# 2022_AESK_UAV_Sensors.net
KiCad netlist of a schematic drawn in Altium Designer
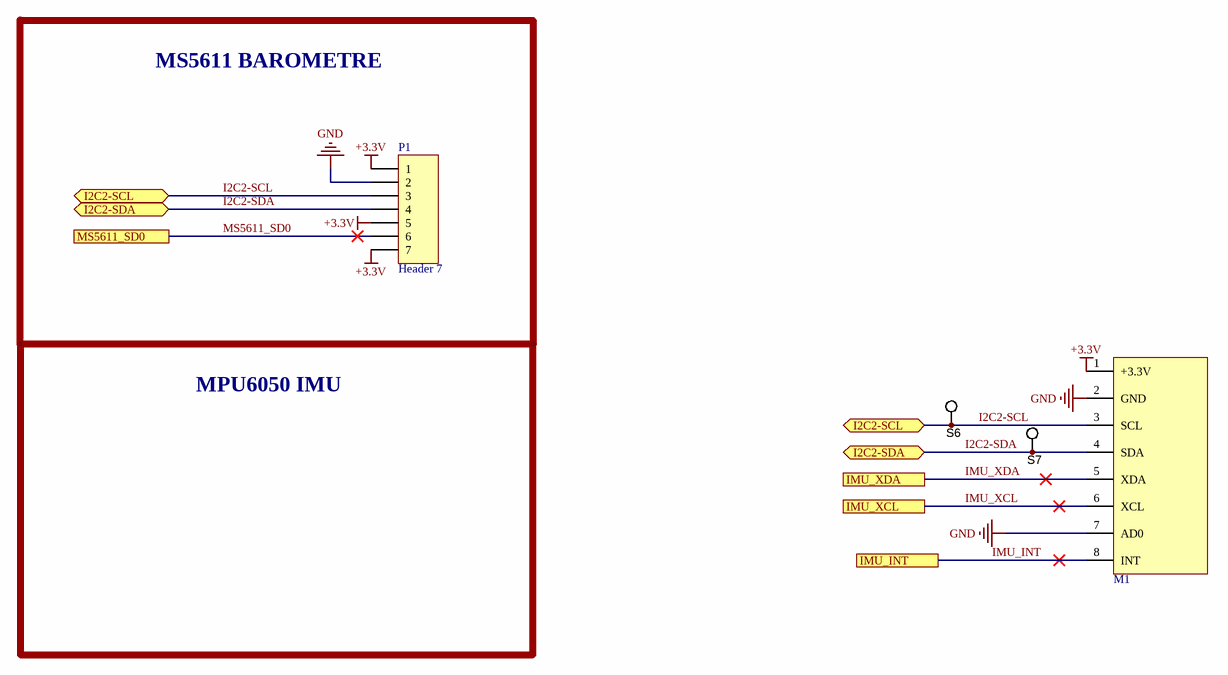
[diagram p0: 2022_AESK_UAV_Sensors.SchDoc]

(export (version "E")
  (design (tool "Eeschema 10.0.6"))
  (components
    (comp (ref "M1")
      (value "MPU-9255(resim ve supplier bilgileri mpu6050dir)")
      (footprint "MPU-9255(GY-87)")
      (libsource (lib "2022_AESK_UAV") (part "MPU-9255(GY-87)"))
    )
    (comp (ref "P1")
      (value "Header 7")
      (footprint "HDR1X7")
      (description "Header, 7-Pin")
      (fields (field (name "PUBLISHER") "Altium Limited"))
      (libsource (lib "Miscellaneous Connectors") (part "Header 7"))
    )
    (comp (ref "S6")
      (value "5002")
      (footprint "Keystone5002")
      (description "Test Point, TH, Miniature, White")
      (fields
        (field (name "MANUFACTURER") "Keystone")
        (field (name "DIGIKEYPARTNUMBER") "5002K-ND")
        (field (name "PUBLISHER") "National Semiconductor")
      )
      (libsource (lib "2022_AESK_UAV") (part "5002"))
    )
    (comp (ref "S7")
      (value "5002")
      (footprint "Keystone5002")
      (description "Test Point, TH, Miniature, White")
      (fields
        (field (name "MANUFACTURER") "Keystone")
        (field (name "DIGIKEYPARTNUMBER") "5002K-ND")
        (field (name "PUBLISHER") "National Semiconductor")
      )
      (libsource (lib "2022_AESK_UAV") (part "5002"))
    )
  )
  (nets
    (net (code "1") (name "+3.3V") (class "Default")
      (node (ref "M1") (pin "1") (pinfunction "+3.3V_1") (pintype "passive"))
      (node (ref "P1") (pin "1") (pinfunction "1_1") (pintype "passive"))
      (node (ref "P1") (pin "5") (pinfunction "5_5") (pintype "passive"))
      (node (ref "P1") (pin "7") (pinfunction "7_7") (pintype "passive"))
    )
    (net (code "2") (name "/I2C2-SCL") (class "Default")
      (node (ref "M1") (pin "3") (pinfunction "SCL_3") (pintype "passive"))
      (node (ref "P1") (pin "3") (pinfunction "3_3") (pintype "passive"))
      (node (ref "S6") (pin "1") (pintype "passive"))
    )
    (net (code "3") (name "/I2C2-SDA") (class "Default")
      (node (ref "M1") (pin "4") (pinfunction "SDA_4") (pintype "passive"))
      (node (ref "P1") (pin "4") (pinfunction "4_4") (pintype "passive"))
      (node (ref "S7") (pin "1") (pintype "passive"))
    )
    (net (code "4") (name "/IMU_INT") (class "Default")
      (node (ref "M1") (pin "8") (pinfunction "INT_8") (pintype "passive"))
    )
    (net (code "5") (name "/IMU_XCL") (class "Default")
      (node (ref "M1") (pin "6") (pinfunction "XCL_6") (pintype "passive"))
    )
    (net (code "6") (name "/IMU_XDA") (class "Default")
      (node (ref "M1") (pin "5") (pinfunction "XDA_5") (pintype "passive"))
    )
    (net (code "7") (name "/MS5611_SD0") (class "Default")
      (node (ref "P1") (pin "6") (pinfunction "6_6") (pintype "passive"))
    )
    (net (code "8") (name "GND") (class "Default")
      (node (ref "M1") (pin "2") (pinfunction "GND_2") (pintype "passive"))
      (node (ref "M1") (pin "7") (pinfunction "AD0_7") (pintype "passive"))
      (node (ref "P1") (pin "2") (pinfunction "2_2") (pintype "passive"))
    )
  )
)
